# MIC-Board.net
KiCad netlist of a schematic drawn in EAGLE
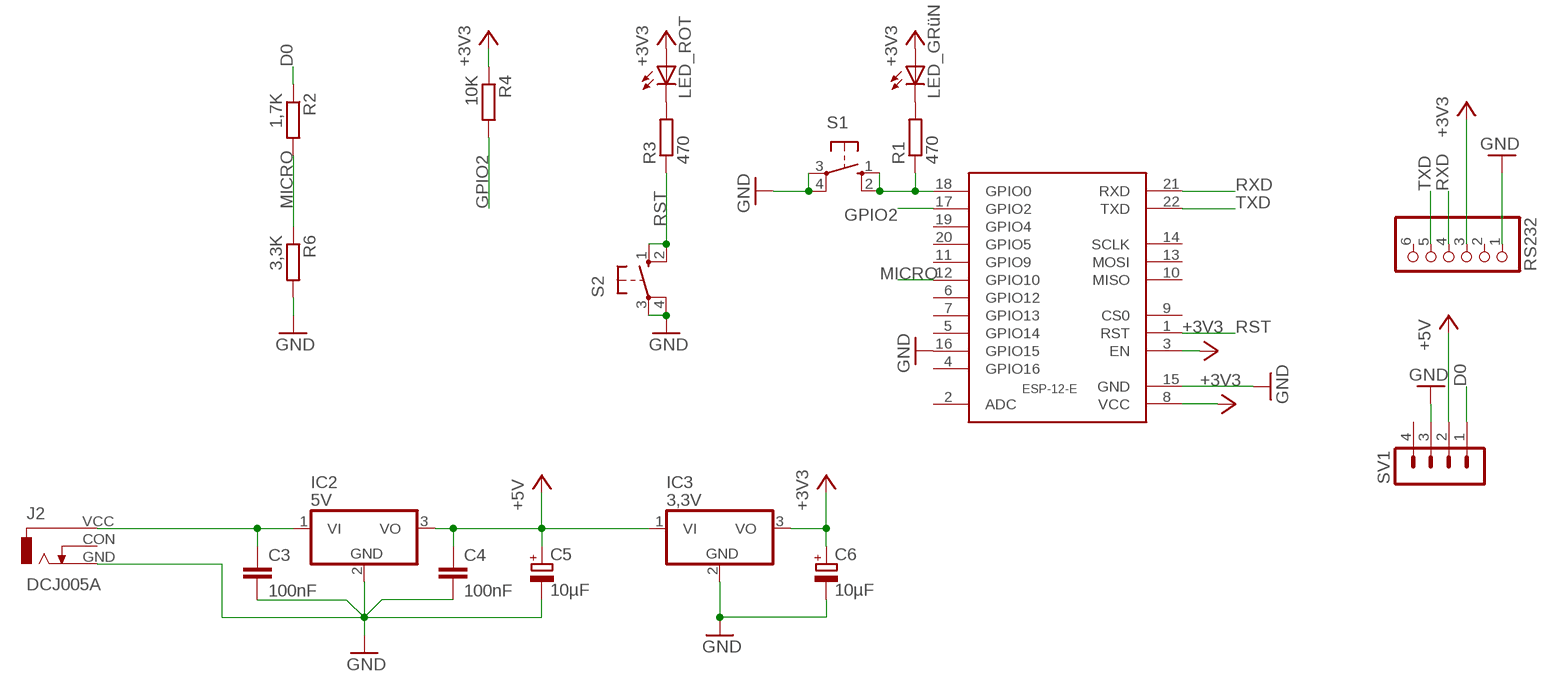
[diagram p0: schematic, sheet 1]

(export (version "E")
  (design (tool "Eeschema 10.0.6"))
  (components
    (comp (ref "C3")
      (value "100nF")
      (footprint "eagle-import:C050-030X075")
      (libsource (lib "eagle-import") (part "C-EU050-030X075"))
    )
    (comp (ref "C4")
      (value "100nF")
      (footprint "eagle-import:C050-030X075")
      (libsource (lib "eagle-import") (part "C-EU050-030X075"))
    )
    (comp (ref "C5")
      (value "10µF")
      (footprint "eagle-import:E2,5-6")
      (libsource (lib "eagle-import") (part "CPOL-EUE2.5-6"))
    )
    (comp (ref "C6")
      (value "10µF")
      (footprint "eagle-import:E2,5-6")
      (libsource (lib "eagle-import") (part "CPOL-EUE2.5-6"))
    )
    (comp (ref "IC2")
      (value "5V")
      (footprint "eagle-import:TO220V")
      (libsource (lib "eagle-import") (part "78TV05"))
    )
    (comp (ref "IC3")
      (value "3,3V")
      (footprint "eagle-import:TO220V")
      (libsource (lib "eagle-import") (part "78TV05"))
    )
    (comp (ref "J2")
      (value "DCJ005A")
      (footprint "eagle-import:DC005A")
      (libsource (lib "eagle-import") (part "DCJ005A"))
    )
    (comp (ref "LED_GRüN")
      (value "LED5MM")
      (footprint "eagle-import:LED5MM")
      (libsource (lib "eagle-import") (part "LED5MM"))
    )
    (comp (ref "LED_ROT")
      (value "LED5MM")
      (footprint "eagle-import:LED5MM")
      (libsource (lib "eagle-import") (part "LED5MM"))
    )
    (comp (ref "R1")
      (value "470")
      (footprint "eagle-import:0207_10")
      (libsource (lib "eagle-import") (part "R-EU_0207/10"))
    )
    (comp (ref "R2")
      (value "1,7K")
      (footprint "eagle-import:0207_10")
      (libsource (lib "eagle-import") (part "R-EU_0207/10"))
    )
    (comp (ref "R3")
      (value "470")
      (footprint "eagle-import:0207_10")
      (libsource (lib "eagle-import") (part "R-EU_0207/10"))
    )
    (comp (ref "R4")
      (value "10K")
      (footprint "eagle-import:0207_10")
      (libsource (lib "eagle-import") (part "R-EU_0207/10"))
    )
    (comp (ref "R6")
      (value "3,3K")
      (footprint "eagle-import:0207_10")
      (libsource (lib "eagle-import") (part "R-EU_0207/10"))
    )
    (comp (ref "RS232")
      (value "PINHD-1X6")
      (footprint "eagle-import:1X06")
      (libsource (lib "eagle-import") (part "PINHD-1X6"))
    )
    (comp (ref "S1")
      (value "10-XX")
      (footprint "eagle-import:B3F-10XX")
      (fields (field (name "MPN") "B3F-1000"))
      (libsource (lib "eagle-import") (part "10-XX"))
    )
    (comp (ref "S2")
      (value "10-XX")
      (footprint "eagle-import:B3F-10XX")
      (fields (field (name "MPN") "B3F-1000"))
      (libsource (lib "eagle-import") (part "10-XX"))
    )
    (comp (ref "SV1")
      (value "MA04-1")
      (footprint "eagle-import:MA04-1")
      (libsource (lib "eagle-import") (part "MA04-1"))
    )
    (comp (ref "U$1")
      (value "ESP-12-E")
      (footprint "eagle-import:ESP-12-E")
      (libsource (lib "eagle-import") (part "ESP-12-E"))
    )
  )
  (nets
    (net (code "1") (name "+3V3") (class "Default")
      (node (ref "C6") (pin "+") (pinfunction "+_+") (pintype "passive"))
      (node (ref "IC3") (pin "3") (pinfunction "VO_3") (pintype "passive"))
      (node (ref "LED_GRüN") (pin "A") (pinfunction "A_A") (pintype "passive"))
      (node (ref "LED_ROT") (pin "A") (pinfunction "A_A") (pintype "passive"))
      (node (ref "R4") (pin "1") (pinfunction "1_1") (pintype "passive"))
      (node (ref "RS232") (pin "3") (pinfunction "3_3") (pintype "passive"))
      (node (ref "U$1") (pin "3") (pinfunction "EN_3") (pintype "bidirectional"))
      (node (ref "U$1") (pin "8") (pinfunction "VCC_8") (pintype "power_in"))
    )
    (net (code "2") (name "+5V") (class "Default")
      (node (ref "C4") (pin "1") (pinfunction "1_1") (pintype "passive"))
      (node (ref "C5") (pin "+") (pinfunction "+_+") (pintype "passive"))
      (node (ref "IC2") (pin "3") (pinfunction "VO_3") (pintype "passive"))
      (node (ref "IC3") (pin "1") (pinfunction "VI_1") (pintype "input"))
      (node (ref "SV1") (pin "2") (pinfunction "2_2") (pintype "passive"))
    )
    (net (code "3") (name "/D0") (class "Default")
      (node (ref "R2") (pin "1") (pinfunction "1_1") (pintype "passive"))
      (node (ref "SV1") (pin "1") (pinfunction "1_1") (pintype "passive"))
    )
    (net (code "4") (name "/GPIO2") (class "Default")
      (node (ref "R4") (pin "2") (pinfunction "2_2") (pintype "passive"))
      (node (ref "U$1") (pin "17") (pinfunction "GPIO2_17") (pintype "bidirectional"))
    )
    (net (code "5") (name "/MICRO") (class "Default")
      (node (ref "R2") (pin "2") (pinfunction "2_2") (pintype "passive"))
      (node (ref "R6") (pin "1") (pinfunction "1_1") (pintype "passive"))
      (node (ref "U$1") (pin "12") (pinfunction "GPIO10_12") (pintype "bidirectional"))
    )
    (net (code "6") (name "/RST") (class "Default")
      (node (ref "R3") (pin "1") (pinfunction "1_1") (pintype "passive"))
      (node (ref "S2") (pin "1") (pinfunction "S_1") (pintype "passive"))
      (node (ref "S2") (pin "2") (pinfunction "S1_2") (pintype "passive"))
      (node (ref "U$1") (pin "1") (pinfunction "RST_1") (pintype "bidirectional"))
    )
    (net (code "7") (name "/RXD") (class "Default")
      (node (ref "RS232") (pin "4") (pinfunction "4_4") (pintype "passive"))
      (node (ref "U$1") (pin "21") (pinfunction "RXD_21") (pintype "bidirectional"))
    )
    (net (code "8") (name "/TXD") (class "Default")
      (node (ref "RS232") (pin "5") (pinfunction "5_5") (pintype "passive"))
      (node (ref "U$1") (pin "22") (pinfunction "TXD_22") (pintype "bidirectional"))
    )
    (net (code "9") (name "GND") (class "Default")
      (node (ref "C3") (pin "2") (pinfunction "2_2") (pintype "passive"))
      (node (ref "C4") (pin "2") (pinfunction "2_2") (pintype "passive"))
      (node (ref "C5") (pin "-") (pinfunction "-_-") (pintype "passive"))
      (node (ref "C6") (pin "-") (pinfunction "-_-") (pintype "passive"))
      (node (ref "IC2") (pin "2") (pinfunction "GND_2") (pintype "passive"))
      (node (ref "IC3") (pin "2") (pinfunction "GND_2") (pintype "passive"))
      (node (ref "J2") (pin "GND") (pinfunction "3_GND") (pintype "passive"))
      (node (ref "R6") (pin "2") (pinfunction "2_2") (pintype "passive"))
      (node (ref "RS232") (pin "1") (pinfunction "1_1") (pintype "passive"))
      (node (ref "S1") (pin "3") (pinfunction "P_3") (pintype "passive"))
      (node (ref "S1") (pin "4") (pinfunction "P1_4") (pintype "passive"))
      (node (ref "S2") (pin "3") (pinfunction "P_3") (pintype "passive"))
      (node (ref "S2") (pin "4") (pinfunction "P1_4") (pintype "passive"))
      (node (ref "SV1") (pin "3") (pinfunction "3_3") (pintype "passive"))
      (node (ref "U$1") (pin "15") (pinfunction "GND_15") (pintype "power_in"))
      (node (ref "U$1") (pin "16") (pinfunction "GPIO15_16") (pintype "bidirectional"))
    )
    (net (code "10") (name "Net-(IC2-VI)") (class "Default")
      (node (ref "C3") (pin "1") (pinfunction "1_1") (pintype "passive"))
      (node (ref "IC2") (pin "1") (pinfunction "VI_1") (pintype "input"))
      (node (ref "J2") (pin "VCC") (pinfunction "1_VCC") (pintype "passive"))
    )
    (net (code "11") (name "Net-(LED_GRüN-C)") (class "Default")
      (node (ref "LED_GRüN") (pin "K") (pinfunction "C_K") (pintype "passive"))
      (node (ref "R1") (pin "2") (pinfunction "2_2") (pintype "passive"))
    )
    (net (code "12") (name "Net-(LED_ROT-C)") (class "Default")
      (node (ref "LED_ROT") (pin "K") (pinfunction "C_K") (pintype "passive"))
      (node (ref "R3") (pin "2") (pinfunction "2_2") (pintype "passive"))
    )
    (net (code "13") (name "Net-(S1-S)") (class "Default")
      (node (ref "R1") (pin "1") (pinfunction "1_1") (pintype "passive"))
      (node (ref "S1") (pin "1") (pinfunction "S_1") (pintype "passive"))
      (node (ref "S1") (pin "2") (pinfunction "S1_2") (pintype "passive"))
      (node (ref "U$1") (pin "18") (pinfunction "GPIO0_18") (pintype "bidirectional"))
    )
    (net (code "14") (name "unconnected-(J2-2-PadCON)") (class "Default")
      (node (ref "J2") (pin "CON") (pinfunction "2_CON") (pintype "passive"))
    )
    (net (code "15") (name "unconnected-(RS232-Pad2)") (class "Default")
      (node (ref "RS232") (pin "2") (pinfunction "2_2") (pintype "passive"))
    )
    (net (code "16") (name "unconnected-(RS232-Pad6)") (class "Default")
      (node (ref "RS232") (pin "6") (pinfunction "6_6") (pintype "passive"))
    )
    (net (code "17") (name "unconnected-(SV1-Pad4)") (class "Default")
      (node (ref "SV1") (pin "4") (pinfunction "4_4") (pintype "passive"))
    )
    (net (code "18") (name "unconnected-(U$1-ADC-Pad2)") (class "Default")
      (node (ref "U$1") (pin "2") (pinfunction "ADC_2") (pintype "bidirectional"))
    )
    (net (code "19") (name "unconnected-(U$1-CS0-Pad9)") (class "Default")
      (node (ref "U$1") (pin "9") (pinfunction "CS0_9") (pintype "bidirectional"))
    )
    (net (code "20") (name "unconnected-(U$1-GPIO4-Pad19)") (class "Default")
      (node (ref "U$1") (pin "19") (pinfunction "GPIO4_19") (pintype "bidirectional"))
    )
    (net (code "21") (name "unconnected-(U$1-GPIO5-Pad20)") (class "Default")
      (node (ref "U$1") (pin "20") (pinfunction "GPIO5_20") (pintype "bidirectional"))
    )
    (net (code "22") (name "unconnected-(U$1-GPIO9-Pad11)") (class "Default")
      (node (ref "U$1") (pin "11") (pinfunction "GPIO9_11") (pintype "bidirectional"))
    )
    (net (code "23") (name "unconnected-(U$1-GPIO12-Pad6)") (class "Default")
      (node (ref "U$1") (pin "6") (pinfunction "GPIO12_6") (pintype "bidirectional"))
    )
    (net (code "24") (name "unconnected-(U$1-GPIO13-Pad7)") (class "Default")
      (node (ref "U$1") (pin "7") (pinfunction "GPIO13_7") (pintype "bidirectional"))
    )
    (net (code "25") (name "unconnected-(U$1-GPIO14-Pad5)") (class "Default")
      (node (ref "U$1") (pin "5") (pinfunction "GPIO14_5") (pintype "bidirectional"))
    )
    (net (code "26") (name "unconnected-(U$1-GPIO16-Pad4)") (class "Default")
      (node (ref "U$1") (pin "4") (pinfunction "GPIO16_4") (pintype "bidirectional"))
    )
    (net (code "27") (name "unconnected-(U$1-MISO-Pad10)") (class "Default")
      (node (ref "U$1") (pin "10") (pinfunction "MISO_10") (pintype "bidirectional"))
    )
    (net (code "28") (name "unconnected-(U$1-MOSI-Pad13)") (class "Default")
      (node (ref "U$1") (pin "13") (pinfunction "MOSI_13") (pintype "bidirectional"))
    )
    (net (code "29") (name "unconnected-(U$1-SCLK-Pad14)") (class "Default")
      (node (ref "U$1") (pin "14") (pinfunction "SCLK_14") (pintype "bidirectional"))
    )
  )
)
